# MCU089B_Connectors.net
KiCad netlist of a schematic drawn in Altium Designer
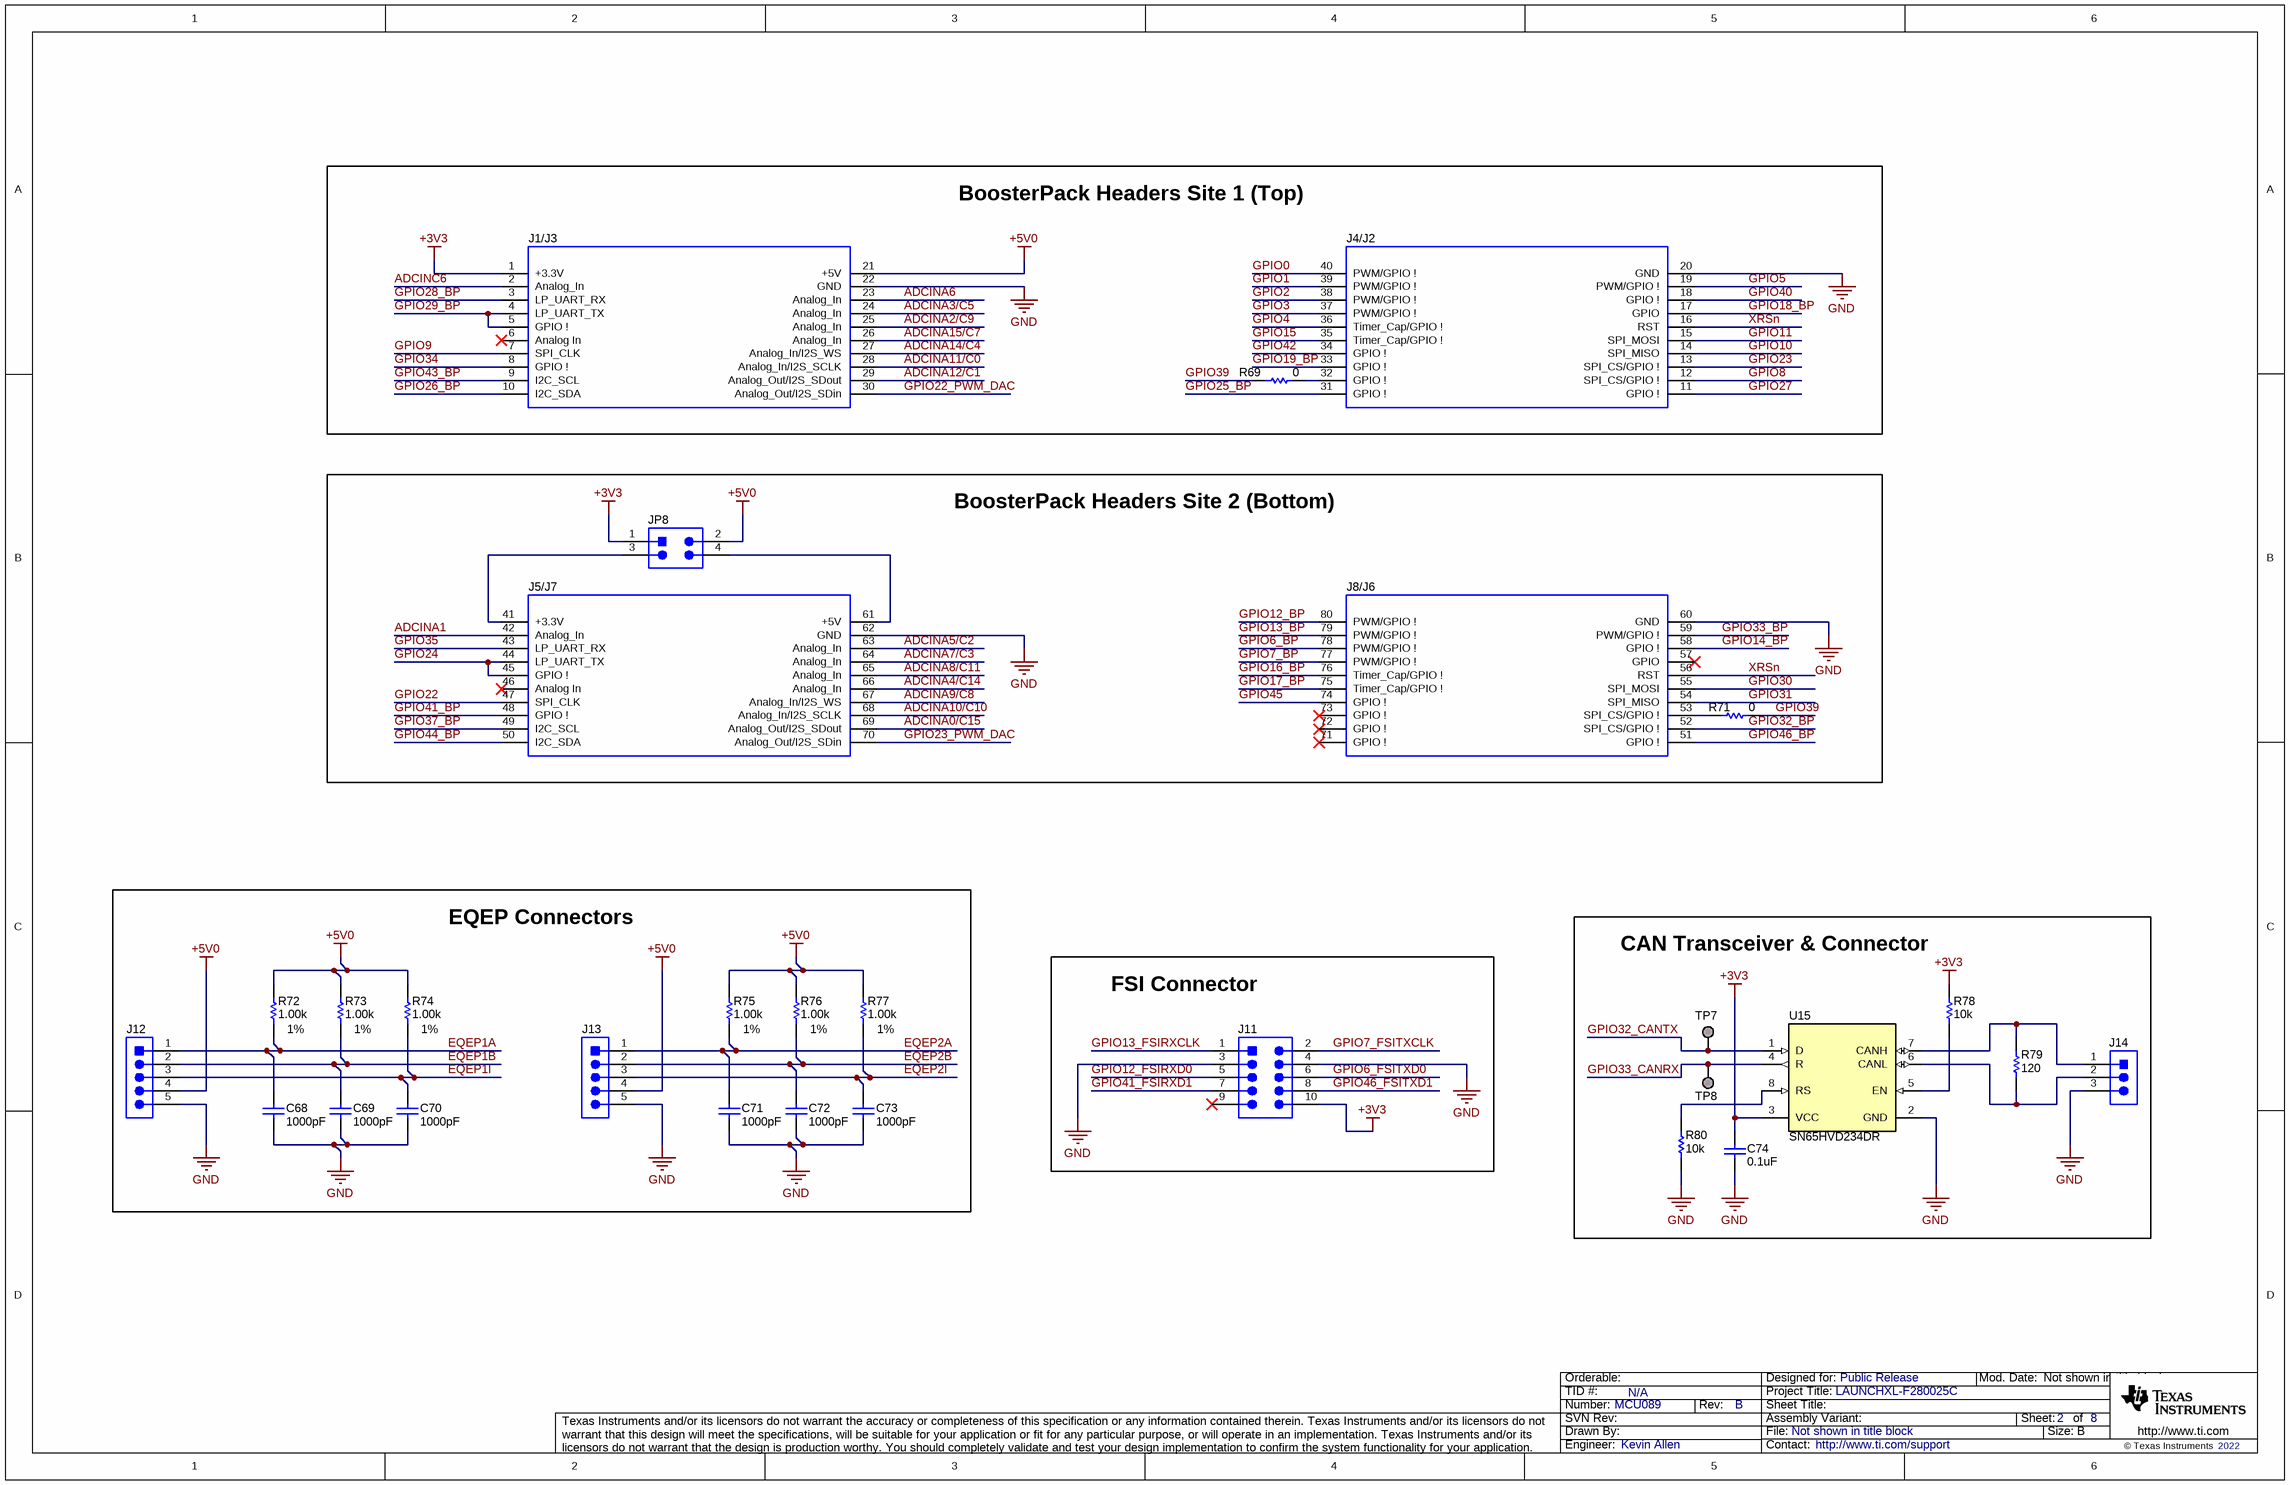
[diagram p0: MCU089B_Connectors.SchDoc]

(export (version "E")
  (design (tool "Eeschema 10.0.6"))
  (components
    (comp (ref "C68")
      (value "885012205061")
      (footprint "0402")
      (description "CAP, CERM, 1000 pF, 50 V, +/- 10%, X7R, 0402")
      (fields
        (field (name "VALUEDISPLAYED") "1000pF")
        (field (name "MANUFACTURER") "Wurth Elektronik")
        (field (name "PUBLISHER") "Texas Instruments")
      )
      (libsource (lib "Altium Vault - TI") (part "Capacitor"))
    )
    (comp (ref "C69")
      (value "885012205061")
      (footprint "0402")
      (description "CAP, CERM, 1000 pF, 50 V, +/- 10%, X7R, 0402")
      (fields
        (field (name "VALUEDISPLAYED") "1000pF")
        (field (name "MANUFACTURER") "Wurth Elektronik")
        (field (name "PUBLISHER") "Texas Instruments")
      )
      (libsource (lib "Altium Vault - TI") (part "Capacitor"))
    )
    (comp (ref "C70")
      (value "885012205061")
      (footprint "0402")
      (description "CAP, CERM, 1000 pF, 50 V, +/- 10%, X7R, 0402")
      (fields
        (field (name "VALUEDISPLAYED") "1000pF")
        (field (name "MANUFACTURER") "Wurth Elektronik")
        (field (name "PUBLISHER") "Texas Instruments")
      )
      (libsource (lib "Altium Vault - TI") (part "Capacitor"))
    )
    (comp (ref "C71")
      (value "885012205061")
      (footprint "0402")
      (description "CAP, CERM, 1000 pF, 50 V, +/- 10%, X7R, 0402")
      (fields
        (field (name "VALUEDISPLAYED") "1000pF")
        (field (name "MANUFACTURER") "Wurth Elektronik")
        (field (name "PUBLISHER") "Texas Instruments")
      )
      (libsource (lib "Altium Vault - TI") (part "Capacitor"))
    )
    (comp (ref "C72")
      (value "885012205061")
      (footprint "0402")
      (description "CAP, CERM, 1000 pF, 50 V, +/- 10%, X7R, 0402")
      (fields
        (field (name "VALUEDISPLAYED") "1000pF")
        (field (name "MANUFACTURER") "Wurth Elektronik")
        (field (name "PUBLISHER") "Texas Instruments")
      )
      (libsource (lib "Altium Vault - TI") (part "Capacitor"))
    )
    (comp (ref "C73")
      (value "885012205061")
      (footprint "0402")
      (description "CAP, CERM, 1000 pF, 50 V, +/- 10%, X7R, 0402")
      (fields
        (field (name "VALUEDISPLAYED") "1000pF")
        (field (name "MANUFACTURER") "Wurth Elektronik")
        (field (name "PUBLISHER") "Texas Instruments")
      )
      (libsource (lib "Altium Vault - TI") (part "Capacitor"))
    )
    (comp (ref "C74")
      (value "GRM155R71A104KA01D")
      (footprint "0402")
      (description "CAP, CERM, 0.1 uF, 10 V, +/- 10%, X7R, 0402")
      (fields
        (field (name "VALUEDISPLAYED") "0.1uF")
        (field (name "MANUFACTURER") "MuRata")
        (field (name "PUBLISHER") "Texas Instruments")
      )
      (libsource (lib "Altium Vault - TI") (part "Capacitor"))
    )
    (comp (ref "J1/J3")
      (value "SSQ-110-03-T-D")
      (footprint "BoosterPack_40pin_J1J3")
      (description "Receptacle, 2.54mm, 10x2, Tin, TH")
      (fields (field (name "ALTERNATE PARTNUMBER") "CRD-081413-A-G") (field (name "MANUFACTURER") "Samtec"))
      (libsource (lib "Altium Vault - TI") (part "BoosterPack_40pin_J1J3"))
    )
    (comp (ref "J4/J2")
      (value "SSQ-110-03-T-D")
      (footprint "BoosterPack_40pin_J2J4")
      (description "Receptacle, 2.54mm, 10x2, Tin, TH")
      (fields (field (name "ALTERNATE PARTNUMBER") "CRD-081413-A-G") (field (name "MANUFACTURER") "Samtec"))
      (libsource (lib "Altium Vault - TI") (part "BoosterPack_40pin_J2J4"))
    )
    (comp (ref "J5/J7")
      (value "SSQ-110-03-T-D")
      (footprint "BoosterPack_40pin_J5J7")
      (description "Receptacle, 2.54mm, 10x2, Tin, TH")
      (fields (field (name "ALTERNATE PARTNUMBER") "CRD-081413-A-G") (field (name "MANUFACTURER") "Samtec"))
      (libsource (lib "Altium Vault - TI") (part "BoosterPack_40pin_J5J7"))
    )
    (comp (ref "J8/J6")
      (value "SSQ-110-03-T-D")
      (footprint "BoosterPack_40pin_J6J8")
      (description "Receptacle, 2.54mm, 10x2, Tin, TH")
      (fields (field (name "ALTERNATE PARTNUMBER") "CRD-081413-A-G") (field (name "MANUFACTURER") "Samtec"))
      (libsource (lib "Altium Vault - TI") (part "BoosterPack_40pin_J6J8"))
    )
    (comp (ref "J11")
      (value "TSW-105-07-G-D")
      (footprint "TSW-105-07-G-D")
      (description "Header, 100mil, 5x2, Gold, TH")
      (fields (field (name "MANUFACTURER") "Samtec"))
      (libsource (lib "Altium Vault - TI") (part "Header_5x2"))
    )
    (comp (ref "J12")
      (value "TSW-105-07-G-S")
      (footprint "TSW-105-07-X-S")
      (description "Header, 100mil, 5x1, Gold, TH")
      (fields (field (name "MANUFACTURER") "Samtec") (field (name "PUBLISHER") "Texas Instruments"))
      (libsource (lib "Altium Vault - TI") (part "Header_5x1"))
    )
    (comp (ref "J13")
      (value "TSW-105-07-G-S")
      (footprint "TSW-105-07-X-S")
      (description "Header, 100mil, 5x1, Gold, TH")
      (fields (field (name "MANUFACTURER") "Samtec") (field (name "PUBLISHER") "Texas Instruments"))
      (libsource (lib "Altium Vault - TI") (part "Header_5x1"))
    )
    (comp (ref "J14")
      (value "61300311121")
      (footprint "WURTH_61300311121")
      (description "Header, 2.54 mm, 3x1, Gold, TH")
      (fields (field (name "MANUFACTURER") "Wurth Elektronik") (field (name "PUBLISHER") "Texas Instruments"))
      (libsource (lib "Altium Vault - TI") (part "CMP-0054796-1"))
    )
    (comp (ref "JP8")
      (value "TSW-102-07-G-D")
      (footprint "TSW-102-07-G-D")
      (description "Header, 100mil, 2x2, Gold, TH")
      (fields (field (name "MANUFACTURER") "Samtec") (field (name "PUBLISHER") "Texas Instruments"))
      (libsource (lib "Altium Vault - TI") (part "Header_2x2"))
    )
    (comp (ref "R69")
      (value "CRCW06030000Z0EA")
      (footprint "0603")
      (description "RES, 0, 5%, 0.1 W, AEC-Q200 Grade 0, 0603")
      (fields (field (name "VALUEDISPLAYED") "0") (field (name "MANUFACTURER") "Vishay-Dale"))
      (libsource (lib "Altium Vault - TI") (part "Resistor"))
    )
    (comp (ref "R71")
      (value "CRCW06030000Z0EA")
      (footprint "0603")
      (description "RES, 0, 5%, 0.1 W, AEC-Q200 Grade 0, 0603")
      (fields (field (name "VALUEDISPLAYED") "0") (field (name "MANUFACTURER") "Vishay-Dale"))
      (libsource (lib "Altium Vault - TI") (part "Resistor"))
    )
    (comp (ref "R72")
      (value "CRCW04021K00FKED")
      (footprint "0402")
      (description "RES, 1.00 k, 1%, 0.063 W, AEC-Q200 Grade 0, 0402")
      (fields
        (field (name "VALUEDISPLAYED") "1.00k")
        (field (name "MANUFACTURER") "Vishay-Dale")
        (field (name "VALUE1") "1%")
      )
      (libsource (lib "Altium Vault - TI") (part "Resistor"))
    )
    (comp (ref "R73")
      (value "CRCW04021K00FKED")
      (footprint "0402")
      (description "RES, 1.00 k, 1%, 0.063 W, AEC-Q200 Grade 0, 0402")
      (fields
        (field (name "VALUEDISPLAYED") "1.00k")
        (field (name "MANUFACTURER") "Vishay-Dale")
        (field (name "VALUE1") "1%")
      )
      (libsource (lib "Altium Vault - TI") (part "Resistor"))
    )
    (comp (ref "R74")
      (value "CRCW04021K00FKED")
      (footprint "0402")
      (description "RES, 1.00 k, 1%, 0.063 W, AEC-Q200 Grade 0, 0402")
      (fields
        (field (name "VALUEDISPLAYED") "1.00k")
        (field (name "MANUFACTURER") "Vishay-Dale")
        (field (name "VALUE1") "1%")
      )
      (libsource (lib "Altium Vault - TI") (part "Resistor"))
    )
    (comp (ref "R75")
      (value "CRCW04021K00FKED")
      (footprint "0402")
      (description "RES, 1.00 k, 1%, 0.063 W, AEC-Q200 Grade 0, 0402")
      (fields
        (field (name "VALUEDISPLAYED") "1.00k")
        (field (name "MANUFACTURER") "Vishay-Dale")
        (field (name "VALUE1") "1%")
      )
      (libsource (lib "Altium Vault - TI") (part "Resistor"))
    )
    (comp (ref "R76")
      (value "CRCW04021K00FKED")
      (footprint "0402")
      (description "RES, 1.00 k, 1%, 0.063 W, AEC-Q200 Grade 0, 0402")
      (fields
        (field (name "VALUEDISPLAYED") "1.00k")
        (field (name "MANUFACTURER") "Vishay-Dale")
        (field (name "VALUE1") "1%")
      )
      (libsource (lib "Altium Vault - TI") (part "Resistor"))
    )
    (comp (ref "R77")
      (value "CRCW04021K00FKED")
      (footprint "0402")
      (description "RES, 1.00 k, 1%, 0.063 W, AEC-Q200 Grade 0, 0402")
      (fields
        (field (name "VALUEDISPLAYED") "1.00k")
        (field (name "MANUFACTURER") "Vishay-Dale")
        (field (name "VALUE1") "1%")
      )
      (libsource (lib "Altium Vault - TI") (part "Resistor"))
    )
    (comp (ref "R78")
      (value "CRCW040210K0JNED")
      (footprint "0402")
      (description "RES, 10 k, 5%, 0.063 W, AEC-Q200 Grade 0, 0402")
      (fields (field (name "VALUEDISPLAYED") "10k") (field (name "MANUFACTURER") "Vishay-Dale"))
      (libsource (lib "Altium Vault - TI") (part "Resistor"))
    )
    (comp (ref "R79")
      (value "RC0603FR-07120RL")
      (footprint "0603")
      (description "RES, 120, 1%, 0.1 W, 0603")
      (fields
        (field (name "VALUEDISPLAYED") "120")
        (field (name "MANUFACTURER") "Yageo America")
        (field (name "PUBLISHER") "Texas Instruments")
      )
      (libsource (lib "Altium Vault - TI") (part "Resistor"))
    )
    (comp (ref "R80")
      (value "CRCW040210K0JNED")
      (footprint "0402")
      (description "RES, 10 k, 5%, 0.063 W, AEC-Q200 Grade 0, 0402")
      (fields (field (name "VALUEDISPLAYED") "10k") (field (name "MANUFACTURER") "Vishay-Dale"))
      (libsource (lib "Altium Vault - TI") (part "Resistor"))
    )
    (comp (ref "TP7")
      (value "TESTPOINT")
      (footprint "TP_50MIL-25MILHOLE")
      (description "TEST POINT.  No entry in BOM.")
      (libsource (lib "Altium Vault - TI") (part "TESTPOINT"))
    )
    (comp (ref "TP8")
      (value "TESTPOINT")
      (footprint "TP_50MIL-25MILHOLE")
      (description "TEST POINT.  No entry in BOM.")
      (libsource (lib "Altium Vault - TI") (part "TESTPOINT"))
    )
    (comp (ref "U15")
      (value "SN65HVD234DR")
      (footprint "D0008A_L")
      (fields (field (name "MANUFACTURER") "Texas Instruments"))
      (libsource (lib "Altium Vault - TI") (part "TI-SN65HVD234-SOIC_D-8"))
    )
  )
  (nets
    (net (code "1") (name "+3V3") (class "Default")
      (node (ref "C74") (pin "2") (pinfunction "2_2") (pintype "passive"))
      (node (ref "J1/J3") (pin "1") (pinfunction "+3.3V_1") (pintype "power_in"))
      (node (ref "J11") (pin "10") (pinfunction "10_10") (pintype "passive"))
      (node (ref "JP8") (pin "1") (pinfunction "1_1") (pintype "passive"))
      (node (ref "R78") (pin "2") (pinfunction "2_2") (pintype "passive"))
      (node (ref "U15") (pin "3") (pinfunction "VCC_3") (pintype "power_in"))
    )
    (net (code "2") (name "+5V0") (class "Default")
      (node (ref "J1/J3") (pin "21") (pinfunction "+5V_21") (pintype "power_in"))
      (node (ref "J12") (pin "4") (pinfunction "4_4") (pintype "passive"))
      (node (ref "J13") (pin "4") (pinfunction "4_4") (pintype "passive"))
      (node (ref "JP8") (pin "2") (pinfunction "2_2") (pintype "passive"))
      (node (ref "R72") (pin "2") (pinfunction "2_2") (pintype "passive"))
      (node (ref "R73") (pin "2") (pinfunction "2_2") (pintype "passive"))
      (node (ref "R74") (pin "2") (pinfunction "2_2") (pintype "passive"))
      (node (ref "R75") (pin "2") (pinfunction "2_2") (pintype "passive"))
      (node (ref "R76") (pin "2") (pinfunction "2_2") (pintype "passive"))
      (node (ref "R77") (pin "2") (pinfunction "2_2") (pintype "passive"))
    )
    (net (code "3") (name "/ADCINA0{slash}C15") (class "Default")
      (node (ref "J5/J7") (pin "69") (pinfunction "Analog_Out/I2S_SDout_69") (pintype "passive"))
    )
    (net (code "4") (name "/ADCINA1") (class "Default")
      (node (ref "J5/J7") (pin "42") (pinfunction "Analog_In_42") (pintype "passive"))
    )
    (net (code "5") (name "/ADCINA2{slash}C9") (class "Default")
      (node (ref "J1/J3") (pin "25") (pinfunction "Analog_In_25") (pintype "passive"))
    )
    (net (code "6") (name "/ADCINA3{slash}C5") (class "Default")
      (node (ref "J1/J3") (pin "24") (pinfunction "Analog_In_24") (pintype "passive"))
    )
    (net (code "7") (name "/ADCINA4{slash}C14") (class "Default")
      (node (ref "J5/J7") (pin "66") (pinfunction "Analog_In_66") (pintype "passive"))
    )
    (net (code "8") (name "/ADCINA5{slash}C2") (class "Default")
      (node (ref "J5/J7") (pin "63") (pinfunction "Analog_In_63") (pintype "passive"))
    )
    (net (code "9") (name "/ADCINA6") (class "Default")
      (node (ref "J1/J3") (pin "23") (pinfunction "Analog_In_23") (pintype "passive"))
    )
    (net (code "10") (name "/ADCINA7{slash}C3") (class "Default")
      (node (ref "J5/J7") (pin "64") (pinfunction "Analog_In_64") (pintype "passive"))
    )
    (net (code "11") (name "/ADCINA8{slash}C11") (class "Default")
      (node (ref "J5/J7") (pin "65") (pinfunction "Analog_In_65") (pintype "passive"))
    )
    (net (code "12") (name "/ADCINA9{slash}C8") (class "Default")
      (node (ref "J5/J7") (pin "67") (pinfunction "Analog_In/I2S_WS_67") (pintype "passive"))
    )
    (net (code "13") (name "/ADCINA10{slash}C10") (class "Default")
      (node (ref "J5/J7") (pin "68") (pinfunction "Analog_In/I2S_SCLK_68") (pintype "passive"))
    )
    (net (code "14") (name "/ADCINA11{slash}C0") (class "Default")
      (node (ref "J1/J3") (pin "28") (pinfunction "Analog_In/I2S_SCLK_28") (pintype "passive"))
    )
    (net (code "15") (name "/ADCINA12{slash}C1") (class "Default")
      (node (ref "J1/J3") (pin "29") (pinfunction "Analog_Out/I2S_SDout_29") (pintype "passive"))
    )
    (net (code "16") (name "/ADCINA14{slash}C4") (class "Default")
      (node (ref "J1/J3") (pin "27") (pinfunction "Analog_In/I2S_WS_27") (pintype "passive"))
    )
    (net (code "17") (name "/ADCINA15{slash}C7") (class "Default")
      (node (ref "J1/J3") (pin "26") (pinfunction "Analog_In_26") (pintype "passive"))
    )
    (net (code "18") (name "/ADCINC6") (class "Default")
      (node (ref "J1/J3") (pin "2") (pinfunction "Analog_In_2") (pintype "passive"))
    )
    (net (code "19") (name "/EQEP1A") (class "Default")
      (node (ref "C68") (pin "1") (pinfunction "1_1") (pintype "passive"))
      (node (ref "J12") (pin "1") (pinfunction "1_1") (pintype "passive"))
      (node (ref "R72") (pin "1") (pinfunction "1_1") (pintype "passive"))
    )
    (net (code "20") (name "/EQEP1B") (class "Default")
      (node (ref "C69") (pin "1") (pinfunction "1_1") (pintype "passive"))
      (node (ref "J12") (pin "2") (pinfunction "2_2") (pintype "passive"))
      (node (ref "R73") (pin "1") (pinfunction "1_1") (pintype "passive"))
    )
    (net (code "21") (name "/EQEP1I") (class "Default")
      (node (ref "C70") (pin "1") (pinfunction "1_1") (pintype "passive"))
      (node (ref "J12") (pin "3") (pinfunction "3_3") (pintype "passive"))
      (node (ref "R74") (pin "1") (pinfunction "1_1") (pintype "passive"))
    )
    (net (code "22") (name "/EQEP2A") (class "Default")
      (node (ref "C71") (pin "1") (pinfunction "1_1") (pintype "passive"))
      (node (ref "J13") (pin "1") (pinfunction "1_1") (pintype "passive"))
      (node (ref "R75") (pin "1") (pinfunction "1_1") (pintype "passive"))
    )
    (net (code "23") (name "/EQEP2B") (class "Default")
      (node (ref "C72") (pin "1") (pinfunction "1_1") (pintype "passive"))
      (node (ref "J13") (pin "2") (pinfunction "2_2") (pintype "passive"))
      (node (ref "R76") (pin "1") (pinfunction "1_1") (pintype "passive"))
    )
    (net (code "24") (name "/EQEP2I") (class "Default")
      (node (ref "C73") (pin "1") (pinfunction "1_1") (pintype "passive"))
      (node (ref "J13") (pin "3") (pinfunction "3_3") (pintype "passive"))
      (node (ref "R77") (pin "1") (pinfunction "1_1") (pintype "passive"))
    )
    (net (code "25") (name "/GPIO0") (class "Default")
      (node (ref "J4/J2") (pin "40") (pinfunction "PWM/GPIO_!_40") (pintype "passive"))
    )
    (net (code "26") (name "/GPIO1") (class "Default")
      (node (ref "J4/J2") (pin "39") (pinfunction "PWM/GPIO_!_39") (pintype "passive"))
    )
    (net (code "27") (name "/GPIO2") (class "Default")
      (node (ref "J4/J2") (pin "38") (pinfunction "PWM/GPIO_!_38") (pintype "passive"))
    )
    (net (code "28") (name "/GPIO3") (class "Default")
      (node (ref "J4/J2") (pin "37") (pinfunction "PWM/GPIO_!_37") (pintype "passive"))
    )
    (net (code "29") (name "/GPIO4") (class "Default")
      (node (ref "J4/J2") (pin "36") (pinfunction "Timer_Cap/GPIO_!_36") (pintype "passive"))
    )
    (net (code "30") (name "/GPIO5") (class "Default")
      (node (ref "J4/J2") (pin "19") (pinfunction "PWM/GPIO_!_19") (pintype "passive"))
    )
    (net (code "31") (name "/GPIO6_BP") (class "Default")
      (node (ref "J8/J6") (pin "78") (pinfunction "PWM/GPIO_!_78") (pintype "passive"))
    )
    (net (code "32") (name "/GPIO6_FSITXD0") (class "Default")
      (node (ref "J11") (pin "6") (pinfunction "6_6") (pintype "passive"))
    )
    (net (code "33") (name "/GPIO7_BP") (class "Default")
      (node (ref "J8/J6") (pin "77") (pinfunction "PWM/GPIO_!_77") (pintype "passive"))
    )
    (net (code "34") (name "/GPIO7_FSITXCLK") (class "Default")
      (node (ref "J11") (pin "2") (pinfunction "2_2") (pintype "passive"))
    )
    (net (code "35") (name "/GPIO8") (class "Default")
      (node (ref "J4/J2") (pin "12") (pinfunction "SPI_CS/GPIO_!_12") (pintype "passive"))
    )
    (net (code "36") (name "/GPIO9") (class "Default")
      (node (ref "J1/J3") (pin "7") (pinfunction "SPI_CLK_7") (pintype "passive"))
    )
    (net (code "37") (name "/GPIO10") (class "Default")
      (node (ref "J4/J2") (pin "14") (pinfunction "SPI_MISO_14") (pintype "passive"))
    )
    (net (code "38") (name "/GPIO11") (class "Default")
      (node (ref "J4/J2") (pin "15") (pinfunction "SPI_MOSI_15") (pintype "passive"))
    )
    (net (code "39") (name "/GPIO12_BP") (class "Default")
      (node (ref "J8/J6") (pin "80") (pinfunction "PWM/GPIO_!_80") (pintype "passive"))
    )
    (net (code "40") (name "/GPIO12_FSIRXD0") (class "Default")
      (node (ref "J11") (pin "5") (pinfunction "5_5") (pintype "passive"))
    )
    (net (code "41") (name "/GPIO13_BP") (class "Default")
      (node (ref "J8/J6") (pin "79") (pinfunction "PWM/GPIO_!_79") (pintype "passive"))
    )
    (net (code "42") (name "/GPIO13_FSIRXCLK") (class "Default")
      (node (ref "J11") (pin "1") (pinfunction "1_1") (pintype "passive"))
    )
    (net (code "43") (name "/GPIO14_BP") (class "Default")
      (node (ref "J8/J6") (pin "58") (pinfunction "GPIO_!_58") (pintype "passive"))
    )
    (net (code "44") (name "/GPIO15") (class "Default")
      (node (ref "J4/J2") (pin "35") (pinfunction "Timer_Cap/GPIO_!_35") (pintype "passive"))
    )
    (net (code "45") (name "/GPIO16_BP") (class "Default")
      (node (ref "J8/J6") (pin "76") (pinfunction "Timer_Cap/GPIO_!_76") (pintype "passive"))
    )
    (net (code "46") (name "/GPIO17_BP") (class "Default")
      (node (ref "J8/J6") (pin "75") (pinfunction "Timer_Cap/GPIO_!_75") (pintype "passive"))
    )
    (net (code "47") (name "/GPIO18_BP") (class "Default")
      (node (ref "J4/J2") (pin "17") (pinfunction "GPIO_17") (pintype "passive"))
    )
    (net (code "48") (name "/GPIO19_BP") (class "Default")
      (node (ref "J4/J2") (pin "33") (pinfunction "GPIO_!_33") (pintype "passive"))
    )
    (net (code "49") (name "/GPIO22") (class "Default")
      (node (ref "J5/J7") (pin "47") (pinfunction "SPI_CLK_47") (pintype "passive"))
    )
    (net (code "50") (name "/GPIO22_PWM_DAC") (class "Default")
      (node (ref "J1/J3") (pin "30") (pinfunction "Analog_Out/I2S_SDin_30") (pintype "passive"))
    )
    (net (code "51") (name "/GPIO23") (class "Default")
      (node (ref "J4/J2") (pin "13") (pinfunction "SPI_CS/GPIO_!_13") (pintype "passive"))
    )
    (net (code "52") (name "/GPIO23_PWM_DAC") (class "Default")
      (node (ref "J5/J7") (pin "70") (pinfunction "Analog_Out/I2S_SDin_70") (pintype "passive"))
    )
    (net (code "53") (name "/GPIO24") (class "Default")
      (node (ref "J5/J7") (pin "44") (pinfunction "LP_UART_TX_44") (pintype "passive"))
      (node (ref "J5/J7") (pin "45") (pinfunction "GPIO_!_45") (pintype "passive"))
    )
    (net (code "54") (name "/GPIO25_BP") (class "Default")
      (node (ref "J4/J2") (pin "31") (pinfunction "GPIO_!_31") (pintype "passive"))
    )
    (net (code "55") (name "/GPIO26_BP") (class "Default")
      (node (ref "J1/J3") (pin "10") (pinfunction "I2C_SDA_10") (pintype "passive"))
    )
    (net (code "56") (name "/GPIO27") (class "Default")
      (node (ref "J4/J2") (pin "11") (pinfunction "GPIO_!_11") (pintype "passive"))
    )
    (net (code "57") (name "/GPIO28_BP") (class "Default")
      (node (ref "J1/J3") (pin "3") (pinfunction "LP_UART_RX_3") (pintype "passive"))
    )
    (net (code "58") (name "/GPIO29_BP") (class "Default")
      (node (ref "J1/J3") (pin "4") (pinfunction "LP_UART_TX_4") (pintype "passive"))
      (node (ref "J1/J3") (pin "5") (pinfunction "GPIO_!_5") (pintype "passive"))
    )
    (net (code "59") (name "/GPIO30") (class "Default")
      (node (ref "J8/J6") (pin "55") (pinfunction "SPI_MOSI_55") (pintype "passive"))
    )
    (net (code "60") (name "/GPIO31") (class "Default")
      (node (ref "J8/J6") (pin "54") (pinfunction "SPI_MISO_54") (pintype "passive"))
    )
    (net (code "61") (name "/GPIO32_BP") (class "Default")
      (node (ref "J8/J6") (pin "52") (pinfunction "SPI_CS/GPIO_!_52") (pintype "passive"))
    )
    (net (code "62") (name "/GPIO32_CANTX") (class "Default")
      (node (ref "TP7") (pin "1") (pintype "passive"))
      (node (ref "U15") (pin "1") (pinfunction "D_1") (pintype "input"))
    )
    (net (code "63") (name "/GPIO33_BP") (class "Default")
      (node (ref "J8/J6") (pin "59") (pinfunction "PWM/GPIO_!_59") (pintype "passive"))
    )
    (net (code "64") (name "/GPIO33_CANRX") (class "Default")
      (node (ref "TP8") (pin "1") (pintype "passive"))
      (node (ref "U15") (pin "4") (pinfunction "R_4") (pintype "output"))
    )
    (net (code "65") (name "/GPIO34") (class "Default")
      (node (ref "J1/J3") (pin "8") (pinfunction "GPIO_!_8") (pintype "passive"))
    )
    (net (code "66") (name "/GPIO35") (class "Default")
      (node (ref "J5/J7") (pin "43") (pinfunction "LP_UART_RX_43") (pintype "passive"))
    )
    (net (code "67") (name "/GPIO37_BP") (class "Default")
      (node (ref "J5/J7") (pin "49") (pinfunction "I2C_SCL_49") (pintype "passive"))
    )
    (net (code "68") (name "/GPIO39") (class "Default")
      (node (ref "R69") (pin "1") (pinfunction "1_1") (pintype "passive"))
      (node (ref "R71") (pin "2") (pinfunction "2_2") (pintype "passive"))
    )
    (net (code "69") (name "/GPIO40") (class "Default")
      (node (ref "J4/J2") (pin "18") (pinfunction "GPIO_!_18") (pintype "passive"))
    )
    (net (code "70") (name "/GPIO41_BP") (class "Default")
      (node (ref "J5/J7") (pin "48") (pinfunction "GPIO_!_48") (pintype "passive"))
    )
    (net (code "71") (name "/GPIO41_FSIRXD1") (class "Default")
      (node (ref "J11") (pin "7") (pinfunction "7_7") (pintype "passive"))
    )
    (net (code "72") (name "/GPIO42") (class "Default")
      (node (ref "J4/J2") (pin "34") (pinfunction "GPIO_!_34") (pintype "passive"))
    )
    (net (code "73") (name "/GPIO43_BP") (class "Default")
      (node (ref "J1/J3") (pin "9") (pinfunction "I2C_SCL_9") (pintype "passive"))
    )
    (net (code "74") (name "/GPIO44_BP") (class "Default")
      (node (ref "J5/J7") (pin "50") (pinfunction "I2C_SDA_50") (pintype "passive"))
    )
    (net (code "75") (name "/GPIO45") (class "Default")
      (node (ref "J8/J6") (pin "74") (pinfunction "GPIO_!_74") (pintype "passive"))
    )
    (net (code "76") (name "/GPIO46_BP") (class "Default")
      (node (ref "J8/J6") (pin "51") (pinfunction "GPIO_!_51") (pintype "passive"))
    )
    (net (code "77") (name "/GPIO46_FSITXD1") (class "Default")
      (node (ref "J11") (pin "8") (pinfunction "8_8") (pintype "passive"))
    )
    (net (code "78") (name "/XRSn") (class "Default")
      (node (ref "J4/J2") (pin "16") (pinfunction "RST_16") (pintype "passive"))
      (node (ref "J8/J6") (pin "56") (pinfunction "RST_56") (pintype "passive"))
    )
    (net (code "79") (name "GND") (class "Default")
      (node (ref "C68") (pin "2") (pinfunction "2_2") (pintype "passive"))
      (node (ref "C69") (pin "2") (pinfunction "2_2") (pintype "passive"))
      (node (ref "C70") (pin "2") (pinfunction "2_2") (pintype "passive"))
      (node (ref "C71") (pin "2") (pinfunction "2_2") (pintype "passive"))
      (node (ref "C72") (pin "2") (pinfunction "2_2") (pintype "passive"))
      (node (ref "C73") (pin "2") (pinfunction "2_2") (pintype "passive"))
      (node (ref "C74") (pin "1") (pinfunction "1_1") (pintype "passive"))
      (node (ref "J1/J3") (pin "22") (pinfunction "GND_22") (pintype "power_in"))
      (node (ref "J11") (pin "3") (pinfunction "3_3") (pintype "passive"))
      (node (ref "J11") (pin "4") (pinfunction "4_4") (pintype "passive"))
      (node (ref "J12") (pin "5") (pinfunction "5_5") (pintype "passive"))
      (node (ref "J13") (pin "5") (pinfunction "5_5") (pintype "passive"))
      (node (ref "J14") (pin "3") (pinfunction "3_3") (pintype "passive"))
      (node (ref "J4/J2") (pin "20") (pinfunction "GND_20") (pintype "power_in"))
      (node (ref "J5/J7") (pin "62") (pinfunction "GND_62") (pintype "power_in"))
      (node (ref "J8/J6") (pin "60") (pinfunction "GND_60") (pintype "power_in"))
      (node (ref "R80") (pin "1") (pinfunction "1_1") (pintype "passive"))
      (node (ref "U15") (pin "2") (pinfunction "GND_2") (pintype "power_in"))
    )
    (net (code "80") (name "Net-(J4/J2-GPIO_!-Pad32)") (class "Default")
      (node (ref "J4/J2") (pin "32") (pinfunction "GPIO_!_32") (pintype "passive"))
      (node (ref "R69") (pin "2") (pinfunction "2_2") (pintype "passive"))
    )
    (net (code "81") (name "Net-(J5/J7-+3.3V)") (class "Default")
      (node (ref "J5/J7") (pin "41") (pinfunction "+3.3V_41") (pintype "power_in"))
      (node (ref "JP8") (pin "3") (pinfunction "3_3") (pintype "passive"))
    )
    (net (code "82") (name "Net-(J5/J7-+5V)") (class "Default")
      (node (ref "J5/J7") (pin "61") (pinfunction "+5V_61") (pintype "power_in"))
      (node (ref "JP8") (pin "4") (pinfunction "4_4") (pintype "passive"))
    )
    (net (code "83") (name "Net-(J8/J6-SPI_CS{slash}GPIO_!-Pad53)") (class "Default")
      (node (ref "J8/J6") (pin "53") (pinfunction "SPI_CS/GPIO_!_53") (pintype "passive"))
      (node (ref "R71") (pin "1") (pinfunction "1_1") (pintype "passive"))
    )
    (net (code "84") (name "Net-(U15-CANH)") (class "Default")
      (node (ref "J14") (pin "1") (pinfunction "1_1") (pintype "passive"))
      (node (ref "R79") (pin "2") (pinfunction "2_2") (pintype "passive"))
      (node (ref "U15") (pin "7") (pinfunction "CANH_7") (pintype "bidirectional"))
    )
    (net (code "85") (name "Net-(U15-CANL)") (class "Default")
      (node (ref "J14") (pin "2") (pinfunction "2_2") (pintype "passive"))
      (node (ref "R79") (pin "1") (pinfunction "1_1") (pintype "passive"))
      (node (ref "U15") (pin "6") (pinfunction "CANL_6") (pintype "bidirectional"))
    )
    (net (code "86") (name "Net-(U15-EN)") (class "Default")
      (node (ref "R78") (pin "1") (pinfunction "1_1") (pintype "passive"))
      (node (ref "U15") (pin "5") (pinfunction "EN_5") (pintype "input"))
    )
    (net (code "87") (name "Net-(U15-RS)") (class "Default")
      (node (ref "R80") (pin "2") (pinfunction "2_2") (pintype "passive"))
      (node (ref "U15") (pin "8") (pinfunction "RS_8") (pintype "input"))
    )
    (net (code "88") (name "unconnected-(J1/J3-Analog_In-Pad6)") (class "Default")
      (node (ref "J1/J3") (pin "6") (pinfunction "Analog_In_6") (pintype "passive+no_connect"))
    )
    (net (code "89") (name "unconnected-(J5/J7-Analog_In-Pad46)") (class "Default")
      (node (ref "J5/J7") (pin "46") (pinfunction "Analog_In_46") (pintype "passive+no_connect"))
    )
    (net (code "90") (name "unconnected-(J8/J6-GPIO-Pad57)") (class "Default")
      (node (ref "J8/J6") (pin "57") (pinfunction "GPIO_57") (pintype "passive+no_connect"))
    )
    (net (code "91") (name "unconnected-(J8/J6-GPIO_!-Pad71)") (class "Default")
      (node (ref "J8/J6") (pin "71") (pinfunction "GPIO_!_71") (pintype "passive+no_connect"))
    )
    (net (code "92") (name "unconnected-(J8/J6-GPIO_!-Pad72)") (class "Default")
      (node (ref "J8/J6") (pin "72") (pinfunction "GPIO_!_72") (pintype "passive+no_connect"))
    )
    (net (code "93") (name "unconnected-(J8/J6-GPIO_!-Pad73)") (class "Default")
      (node (ref "J8/J6") (pin "73") (pinfunction "GPIO_!_73") (pintype "passive+no_connect"))
    )
    (net (code "94") (name "unconnected-(J11-Pad9)") (class "Default")
      (node (ref "J11") (pin "9") (pinfunction "9_9") (pintype "passive+no_connect"))
    )
  )
)
